# Mainsch.net
KiCad netlist of a schematic drawn in EAGLE
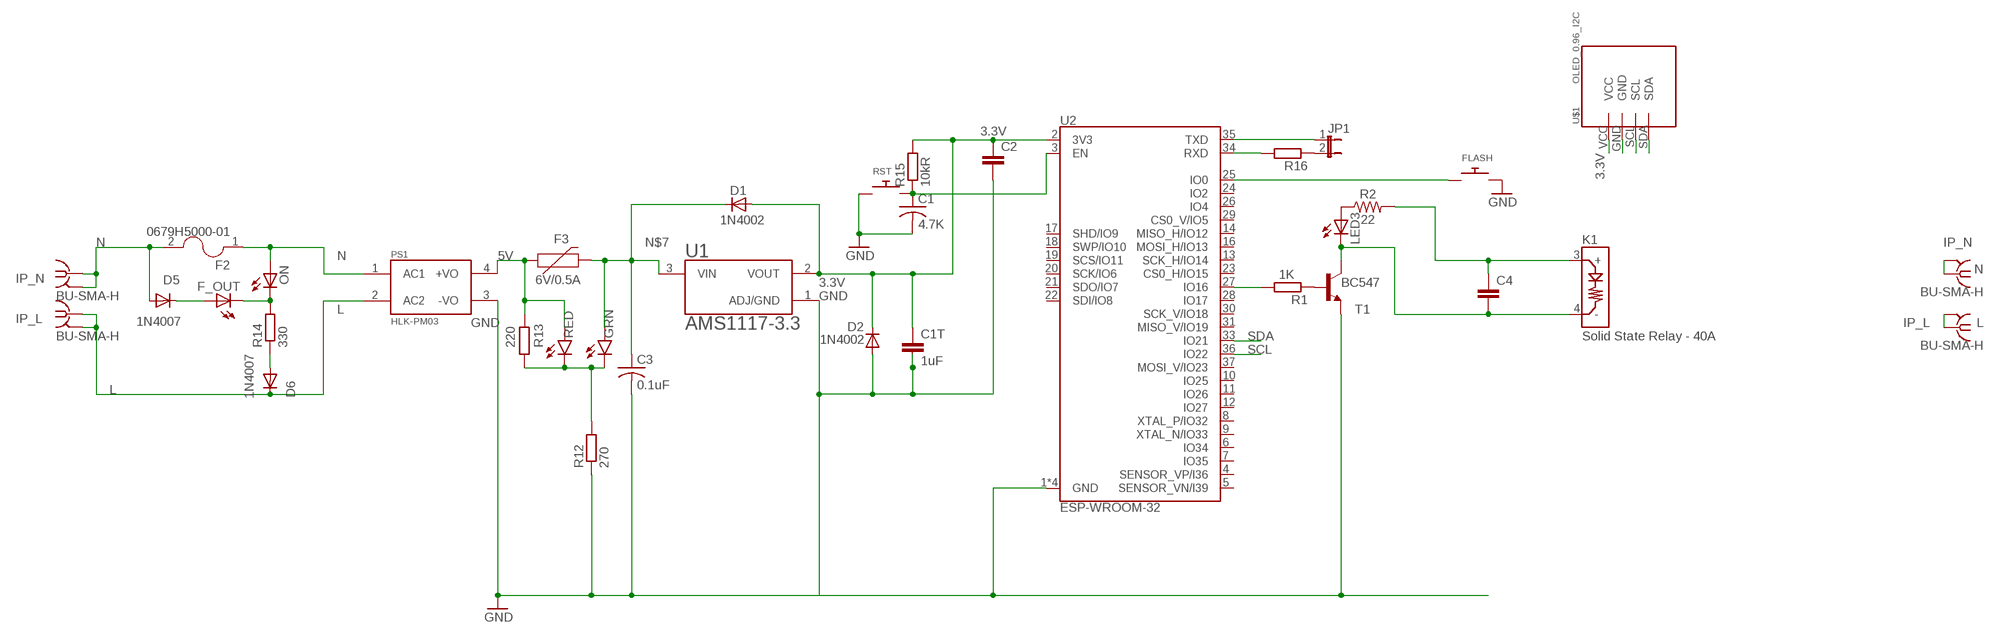
[diagram p0: schematic, sheet 1]

(export (version "E")
  (design (tool "Eeschema 10.0.6"))
  (components
    (comp (ref "C1")
      (value "4.7K")
      (footprint "eagle-import:C0805K")
      (libsource (lib "eagle-import") (part "C-USC0805K"))
    )
    (comp (ref "C1T")
      (value "1uF")
      (footprint "eagle-import:C0805")
      (libsource (lib "eagle-import") (part "C-EUC0805"))
    )
    (comp (ref "C2")
      (value "C-EUC0805")
      (footprint "eagle-import:C0805")
      (libsource (lib "eagle-import") (part "C-EUC0805"))
    )
    (comp (ref "C3")
      (value "0.1uF")
      (footprint "eagle-import:C0805K")
      (libsource (lib "eagle-import") (part "C-USC0805K"))
    )
    (comp (ref "C4")
      (value "C-EUC0805")
      (footprint "eagle-import:C0805")
      (libsource (lib "eagle-import") (part "C-EUC0805"))
    )
    (comp (ref "D1")
      (value "1N4002")
      (footprint "eagle-import:DO41-10")
      (libsource (lib "eagle-import") (part "diode_1N4004"))
    )
    (comp (ref "D2")
      (value "1N4002")
      (footprint "eagle-import:DO41-10")
      (libsource (lib "eagle-import") (part "diode_1N4004"))
    )
    (comp (ref "D5")
      (value "1N4007")
      (footprint "eagle-import:DO41-10")
      (libsource (lib "eagle-import") (part "1N4004"))
    )
    (comp (ref "D6")
      (value "1N4007")
      (footprint "eagle-import:DO41-10")
      (libsource (lib "eagle-import") (part "1N4004"))
    )
    (comp (ref "F2")
      (value "0679H5000-01")
      (footprint "eagle-import:FUSC6125X279N")
      (fields (field (name "MF") "Bel Fuse"))
      (libsource (lib "eagle-import") (part "0679H5000-01"))
    )
    (comp (ref "F3")
      (value "6V/0.5A")
      (footprint "eagle-import:1206")
      (libsource (lib "eagle-import") (part "PPTC_6V500MA-2"))
    )
    (comp (ref "FLASH")
      (value "SWITCH_PUSHBUTTONC&K_KSS")
      (footprint "eagle-import:BTN_CK_KSS")
      (libsource (lib "eagle-import") (part "SWITCH_PUSHBUTTONC&K_KSS"))
    )
    (comp (ref "F_OUT")
      (value "LEDCHIPLED_1206")
      (footprint "eagle-import:CHIPLED_1206")
      (libsource (lib "eagle-import") (part "LEDCHIPLED_1206"))
    )
    (comp (ref "GRN")
      (value "LED1206")
      (footprint "eagle-import:LED-1206")
      (libsource (lib "eagle-import") (part "LED1206"))
    )
    (comp (ref "IP_L")
      (value "BU-SMA-H")
      (footprint "eagle-import:BU-SMA-H")
      (libsource (lib "eagle-import") (part "BU-SMA-H"))
    )
    (comp (ref "IP_N")
      (value "BU-SMA-H")
      (footprint "eagle-import:BU-SMA-H")
      (libsource (lib "eagle-import") (part "BU-SMA-H"))
    )
    (comp (ref "JP1")
      (value "JP1E")
      (footprint "eagle-import:JP1")
      (libsource (lib "eagle-import") (part "JP1E"))
    )
    (comp (ref "K1")
      (value "Solid State Relay - 40A")
      (footprint "eagle-import:SSR-40DA-H")
      (libsource (lib "eagle-import") (part "SOLID_STATE_RELAY_SSR-40DA-H"))
    )
    (comp (ref "L")
      (value "BU-SMA-H")
      (footprint "eagle-import:BU-SMA-H")
      (libsource (lib "eagle-import") (part "BU-SMA-H"))
    )
    (comp (ref "LED3")
      (value "LEDCHIPLED_1206")
      (footprint "eagle-import:CHIPLED_1206")
      (libsource (lib "eagle-import") (part "LEDCHIPLED_1206"))
    )
    (comp (ref "N")
      (value "BU-SMA-H")
      (footprint "eagle-import:BU-SMA-H")
      (libsource (lib "eagle-import") (part "BU-SMA-H"))
    )
    (comp (ref "ON")
      (value "LEDCHIPLED_1206")
      (footprint "eagle-import:CHIPLED_1206")
      (libsource (lib "eagle-import") (part "LEDCHIPLED_1206"))
    )
    (comp (ref "PS1")
      (value "HLK-PM03")
      (footprint "eagle-import:CONV_HLK-PM03")
      (fields (field (name "MF") "Hi-link"))
      (libsource (lib "eagle-import") (part "HLK-PM03"))
    )
    (comp (ref "R1")
      (value "1K")
      (footprint "eagle-import:R1206")
      (libsource (lib "eagle-import") (part "resistor_348_R-EU_R1206"))
    )
    (comp (ref "R2")
      (value "22")
      (footprint "eagle-import:0603")
      (libsource (lib "eagle-import") (part "22OHM-0603-1/10W-1%"))
    )
    (comp (ref "R12")
      (value "270")
      (footprint "eagle-import:R0805")
      (libsource (lib "eagle-import") (part "R-EU_R0805"))
    )
    (comp (ref "R13")
      (value "220")
      (footprint "eagle-import:R0805")
      (libsource (lib "eagle-import") (part "R-EU_R0805"))
    )
    (comp (ref "R14")
      (value "330")
      (footprint "eagle-import:R0805")
      (libsource (lib "eagle-import") (part "R-EU_R0805"))
    )
    (comp (ref "R15")
      (value "10kR")
      (footprint "eagle-import:R0805")
      (libsource (lib "eagle-import") (part "R-EU_R0805"))
    )
    (comp (ref "R16")
      (value "R-EU_R0805")
      (footprint "eagle-import:R0805")
      (libsource (lib "eagle-import") (part "R-EU_R0805"))
    )
    (comp (ref "RED")
      (value "LED1206")
      (footprint "eagle-import:LED-1206")
      (libsource (lib "eagle-import") (part "LED1206"))
    )
    (comp (ref "RST")
      (value "SWITCH_PUSHBUTTONC&K_KSS")
      (footprint "eagle-import:BTN_CK_KSS")
      (libsource (lib "eagle-import") (part "SWITCH_PUSHBUTTONC&K_KSS"))
    )
    (comp (ref "T1")
      (value "BC547")
      (footprint "eagle-import:TO92")
      (libsource (lib "eagle-import") (part "BC547"))
    )
    (comp (ref "U$1")
      (value "OLED_0.96_I2C")
      (footprint "eagle-import:OLED_0.96_I2C")
      (libsource (lib "eagle-import") (part "OLED_0.96_I2C"))
    )
    (comp (ref "U1")
      (value "AMS1117-3.3")
      (footprint "eagle-import:SOT229P700X180-4N")
      (fields (field (name "MF") "AMD"))
      (libsource (lib "eagle-import") (part "AMS1117-3.3"))
    )
    (comp (ref "U2")
      (value "ESP-WROOM-32")
      (footprint "eagle-import:ESP-WROOM-32")
      (libsource (lib "eagle-import") (part "ESP-WROOM-32"))
    )
  )
  (nets
    (net (code "1") (name "/3.3V") (class "Default")
      (node (ref "C1T") (pin "1") (pinfunction "1_1") (pintype "passive"))
      (node (ref "C2") (pin "1") (pinfunction "1_1") (pintype "passive"))
      (node (ref "D1") (pin "A") (pinfunction "A_A") (pintype "passive"))
      (node (ref "D2") (pin "C") (pinfunction "C_C") (pintype "passive"))
      (node (ref "R15") (pin "2") (pinfunction "2_2") (pintype "passive"))
      (node (ref "U$1") (pin "VCC") (pinfunction "VCC_VCC") (pintype "bidirectional"))
      (node (ref "U1") (pin "2") (pinfunction "VOUT_2") (pintype "output"))
      (node (ref "U2") (pin "2") (pinfunction "3V3_2") (pintype "bidirectional"))
    )
    (net (code "2") (name "/5V") (class "Default")
      (node (ref "F3") (pin "1") (pinfunction "1_1") (pintype "bidirectional"))
      (node (ref "PS1") (pin "4") (pinfunction "+VO_4") (pintype "output"))
      (node (ref "R13") (pin "2") (pinfunction "2_2") (pintype "passive"))
      (node (ref "RED") (pin "A") (pinfunction "A_A") (pintype "passive"))
    )
    (net (code "3") (name "/IP_L") (class "Default")
      (node (ref "L") (pin "1") (pinfunction "1_1") (pintype "passive"))
      (node (ref "L") (pin "2") (pinfunction "2_2") (pintype "passive"))
      (node (ref "L") (pin "3") (pinfunction "2_3") (pintype "passive"))
      (node (ref "L") (pin "4") (pinfunction "2_4") (pintype "passive"))
      (node (ref "L") (pin "5") (pinfunction "2_5") (pintype "passive"))
    )
    (net (code "4") (name "/IP_N") (class "Default")
      (node (ref "N") (pin "1") (pinfunction "1_1") (pintype "passive"))
      (node (ref "N") (pin "2") (pinfunction "2_2") (pintype "passive"))
      (node (ref "N") (pin "3") (pinfunction "2_3") (pintype "passive"))
      (node (ref "N") (pin "4") (pinfunction "2_4") (pintype "passive"))
      (node (ref "N") (pin "5") (pinfunction "2_5") (pintype "passive"))
    )
    (net (code "5") (name "/L") (class "Default")
      (node (ref "D6") (pin "C") (pinfunction "C_C") (pintype "passive"))
      (node (ref "IP_L") (pin "1") (pinfunction "1_1") (pintype "passive"))
      (node (ref "IP_L") (pin "2") (pinfunction "2_2") (pintype "passive"))
      (node (ref "IP_L") (pin "3") (pinfunction "2_3") (pintype "passive"))
      (node (ref "IP_L") (pin "4") (pinfunction "2_4") (pintype "passive"))
      (node (ref "IP_L") (pin "5") (pinfunction "2_5") (pintype "passive"))
      (node (ref "PS1") (pin "2") (pinfunction "AC2_2") (pintype "input"))
    )
    (net (code "6") (name "/N") (class "Default")
      (node (ref "D5") (pin "A") (pinfunction "A_A") (pintype "passive"))
      (node (ref "F2") (pin "1") (pinfunction "1_1") (pintype "passive"))
      (node (ref "F2") (pin "2") (pinfunction "2_2") (pintype "passive"))
      (node (ref "IP_N") (pin "1") (pinfunction "1_1") (pintype "passive"))
      (node (ref "IP_N") (pin "2") (pinfunction "2_2") (pintype "passive"))
      (node (ref "IP_N") (pin "3") (pinfunction "2_3") (pintype "passive"))
      (node (ref "IP_N") (pin "4") (pinfunction "2_4") (pintype "passive"))
      (node (ref "IP_N") (pin "5") (pinfunction "2_5") (pintype "passive"))
      (node (ref "ON") (pin "A") (pinfunction "A_A") (pintype "passive"))
      (node (ref "PS1") (pin "1") (pinfunction "AC1_1") (pintype "input"))
    )
    (net (code "7") (name "/N$7") (class "Default")
      (node (ref "C3") (pin "1") (pinfunction "1_1") (pintype "passive"))
      (node (ref "D1") (pin "C") (pinfunction "C_C") (pintype "passive"))
      (node (ref "F3") (pin "2") (pinfunction "2_2") (pintype "bidirectional"))
      (node (ref "GRN") (pin "A") (pinfunction "A_A") (pintype "passive"))
      (node (ref "U1") (pin "3") (pinfunction "VIN_3") (pintype "input"))
    )
    (net (code "8") (name "/SCL") (class "Default")
      (node (ref "U$1") (pin "SCL") (pinfunction "SCL_SCL") (pintype "bidirectional"))
      (node (ref "U2") (pin "36") (pinfunction "IO22_36") (pintype "bidirectional"))
    )
    (net (code "9") (name "/SDA") (class "Default")
      (node (ref "U$1") (pin "SDA") (pinfunction "SDA_SDA") (pintype "bidirectional"))
      (node (ref "U2") (pin "33") (pinfunction "IO21_33") (pintype "bidirectional"))
    )
    (net (code "10") (name "GND") (class "Default")
      (node (ref "C1") (pin "2") (pinfunction "2_2") (pintype "passive"))
      (node (ref "C1T") (pin "2") (pinfunction "2_2") (pintype "passive"))
      (node (ref "C2") (pin "2") (pinfunction "2_2") (pintype "passive"))
      (node (ref "C3") (pin "2") (pinfunction "2_2") (pintype "passive"))
      (node (ref "D2") (pin "A") (pinfunction "A_A") (pintype "passive"))
      (node (ref "FLASH") (pin "P$2") (pinfunction "P$2_P$2") (pintype "passive"))
      (node (ref "PS1") (pin "3") (pinfunction "-VO_3") (pintype "output"))
      (node (ref "R12") (pin "1") (pinfunction "1_1") (pintype "passive"))
      (node (ref "RST") (pin "P$1") (pinfunction "P$1_P$1") (pintype "passive"))
      (node (ref "T1") (pin "1") (pinfunction "E_1") (pintype "passive"))
      (node (ref "U$1") (pin "GND") (pinfunction "GND_GND") (pintype "bidirectional"))
      (node (ref "U1") (pin "1") (pinfunction "ADJ/GND_1") (pintype "power_in"))
      (node (ref "U2") (pin "1") (pinfunction "GND_1") (pintype "bidirectional"))
      (node (ref "U2") (pin "15") (pinfunction "GND_15") (pintype "bidirectional"))
      (node (ref "U2") (pin "38") (pinfunction "GND_38") (pintype "bidirectional"))
      (node (ref "U2") (pin "GND") (pinfunction "GND_GND") (pintype "bidirectional"))
    )
    (net (code "11") (name "Net-(D5-PadC)") (class "Default")
      (node (ref "D5") (pin "C") (pinfunction "C_C") (pintype "passive"))
      (node (ref "F_OUT") (pin "A") (pinfunction "A_A") (pintype "passive"))
    )
    (net (code "12") (name "Net-(D6-PadA)") (class "Default")
      (node (ref "D6") (pin "A") (pinfunction "A_A") (pintype "passive"))
      (node (ref "R14") (pin "1") (pinfunction "1_1") (pintype "passive"))
    )
    (net (code "13") (name "Net-(F_OUT-PadC)") (class "Default")
      (node (ref "F_OUT") (pin "C") (pinfunction "C_C") (pintype "passive"))
      (node (ref "ON") (pin "C") (pinfunction "C_C") (pintype "passive"))
      (node (ref "R14") (pin "2") (pinfunction "2_2") (pintype "passive"))
    )
    (net (code "14") (name "Net-(GRN-PadC)") (class "Default")
      (node (ref "GRN") (pin "C") (pinfunction "C_C") (pintype "passive"))
      (node (ref "R12") (pin "2") (pinfunction "2_2") (pintype "passive"))
      (node (ref "R13") (pin "1") (pinfunction "1_1") (pintype "passive"))
      (node (ref "RED") (pin "C") (pinfunction "C_C") (pintype "passive"))
    )
    (net (code "15") (name "Net-(JP1-Pad2)") (class "Default")
      (node (ref "JP1") (pin "2") (pinfunction "2_2") (pintype "passive"))
      (node (ref "R16") (pin "1") (pinfunction "1_1") (pintype "passive"))
    )
    (net (code "16") (name "Net-(K1-+)") (class "Default")
      (node (ref "C4") (pin "1") (pinfunction "1_1") (pintype "passive"))
      (node (ref "K1") (pin "3") (pinfunction "+_3") (pintype "bidirectional"))
      (node (ref "R2") (pin "2") (pinfunction "2_2") (pintype "passive"))
    )
    (net (code "17") (name "Net-(K1--)") (class "Default")
      (node (ref "C4") (pin "2") (pinfunction "2_2") (pintype "passive"))
      (node (ref "K1") (pin "4") (pinfunction "-_4") (pintype "bidirectional"))
      (node (ref "LED3") (pin "C") (pinfunction "C_C") (pintype "passive"))
      (node (ref "T1") (pin "3") (pinfunction "C_3") (pintype "passive"))
    )
    (net (code "18") (name "Net-(LED3-PadA)") (class "Default")
      (node (ref "LED3") (pin "A") (pinfunction "A_A") (pintype "passive"))
      (node (ref "R2") (pin "1") (pinfunction "1_1") (pintype "passive"))
    )
    (net (code "19") (name "Net-(T1-B)") (class "Default")
      (node (ref "R1") (pin "1") (pinfunction "1_1") (pintype "passive"))
      (node (ref "T1") (pin "2") (pinfunction "B_2") (pintype "passive"))
    )
    (net (code "20") (name "Net-(U2-EN)") (class "Default")
      (node (ref "C1") (pin "1") (pinfunction "1_1") (pintype "passive"))
      (node (ref "R15") (pin "1") (pinfunction "1_1") (pintype "passive"))
      (node (ref "RST") (pin "P$2") (pinfunction "P$2_P$2") (pintype "passive"))
      (node (ref "U2") (pin "3") (pinfunction "EN_3") (pintype "bidirectional"))
    )
    (net (code "21") (name "Net-(U2-IO0)") (class "Default")
      (node (ref "FLASH") (pin "P$1") (pinfunction "P$1_P$1") (pintype "passive"))
      (node (ref "U2") (pin "25") (pinfunction "IO0_25") (pintype "bidirectional"))
    )
    (net (code "22") (name "Net-(U2-IO16)") (class "Default")
      (node (ref "R1") (pin "2") (pinfunction "2_2") (pintype "passive"))
      (node (ref "U2") (pin "27") (pinfunction "IO16_27") (pintype "bidirectional"))
    )
    (net (code "23") (name "Net-(U2-RXD)") (class "Default")
      (node (ref "R16") (pin "2") (pinfunction "2_2") (pintype "passive"))
      (node (ref "U2") (pin "34") (pinfunction "RXD_34") (pintype "bidirectional"))
    )
    (net (code "24") (name "Net-(U2-TXD)") (class "Default")
      (node (ref "JP1") (pin "1") (pinfunction "1_1") (pintype "passive"))
      (node (ref "U2") (pin "35") (pinfunction "TXD_35") (pintype "bidirectional"))
    )
    (net (code "25") (name "unconnected-(U2-CS0_H{slash}IO15-Pad23)") (class "Default")
      (node (ref "U2") (pin "23") (pinfunction "CS0_H/IO15_23") (pintype "bidirectional"))
    )
    (net (code "26") (name "unconnected-(U2-CS0_V{slash}IO5-Pad29)") (class "Default")
      (node (ref "U2") (pin "29") (pinfunction "CS0_V/IO5_29") (pintype "bidirectional"))
    )
    (net (code "27") (name "unconnected-(U2-IO2-Pad24)") (class "Default")
      (node (ref "U2") (pin "24") (pinfunction "IO2_24") (pintype "bidirectional"))
    )
    (net (code "28") (name "unconnected-(U2-IO4-Pad26)") (class "Default")
      (node (ref "U2") (pin "26") (pinfunction "IO4_26") (pintype "bidirectional"))
    )
    (net (code "29") (name "unconnected-(U2-IO17-Pad28)") (class "Default")
      (node (ref "U2") (pin "28") (pinfunction "IO17_28") (pintype "bidirectional"))
    )
    (net (code "30") (name "unconnected-(U2-IO25-Pad10)") (class "Default")
      (node (ref "U2") (pin "10") (pinfunction "IO25_10") (pintype "bidirectional"))
    )
    (net (code "31") (name "unconnected-(U2-IO26-Pad11)") (class "Default")
      (node (ref "U2") (pin "11") (pinfunction "IO26_11") (pintype "bidirectional"))
    )
    (net (code "32") (name "unconnected-(U2-IO27-Pad12)") (class "Default")
      (node (ref "U2") (pin "12") (pinfunction "IO27_12") (pintype "bidirectional"))
    )
    (net (code "33") (name "unconnected-(U2-IO34-Pad6)") (class "Default")
      (node (ref "U2") (pin "6") (pinfunction "IO34_6") (pintype "bidirectional"))
    )
    (net (code "34") (name "unconnected-(U2-IO35-Pad7)") (class "Default")
      (node (ref "U2") (pin "7") (pinfunction "IO35_7") (pintype "bidirectional"))
    )
    (net (code "35") (name "unconnected-(U2-MISO_H{slash}IO12-Pad14)") (class "Default")
      (node (ref "U2") (pin "14") (pinfunction "MISO_H/IO12_14") (pintype "bidirectional"))
    )
    (net (code "36") (name "unconnected-(U2-MISO_V{slash}IO19-Pad31)") (class "Default")
      (node (ref "U2") (pin "31") (pinfunction "MISO_V/IO19_31") (pintype "bidirectional"))
    )
    (net (code "37") (name "unconnected-(U2-MOSI_H{slash}IO13-Pad16)") (class "Default")
      (node (ref "U2") (pin "16") (pinfunction "MOSI_H/IO13_16") (pintype "bidirectional"))
    )
    (net (code "38") (name "unconnected-(U2-MOSI_V{slash}IO23-Pad37)") (class "Default")
      (node (ref "U2") (pin "37") (pinfunction "MOSI_V/IO23_37") (pintype "bidirectional"))
    )
    (net (code "39") (name "unconnected-(U2-SCK_H{slash}IO14-Pad13)") (class "Default")
      (node (ref "U2") (pin "13") (pinfunction "SCK_H/IO14_13") (pintype "bidirectional"))
    )
    (net (code "40") (name "unconnected-(U2-SCK_V{slash}IO18-Pad30)") (class "Default")
      (node (ref "U2") (pin "30") (pinfunction "SCK_V/IO18_30") (pintype "bidirectional"))
    )
    (net (code "41") (name "unconnected-(U2-SCK{slash}IO6-Pad20)") (class "Default")
      (node (ref "U2") (pin "20") (pinfunction "SCK/IO6_20") (pintype "bidirectional"))
    )
    (net (code "42") (name "unconnected-(U2-SCS{slash}IO11-Pad19)") (class "Default")
      (node (ref "U2") (pin "19") (pinfunction "SCS/IO11_19") (pintype "bidirectional"))
    )
    (net (code "43") (name "unconnected-(U2-SDI{slash}IO8-Pad22)") (class "Default")
      (node (ref "U2") (pin "22") (pinfunction "SDI/IO8_22") (pintype "bidirectional"))
    )
    (net (code "44") (name "unconnected-(U2-SDO{slash}IO7-Pad21)") (class "Default")
      (node (ref "U2") (pin "21") (pinfunction "SDO/IO7_21") (pintype "bidirectional"))
    )
    (net (code "45") (name "unconnected-(U2-SENSOR_VN{slash}I39-Pad5)") (class "Default")
      (node (ref "U2") (pin "5") (pinfunction "SENSOR_VN/I39_5") (pintype "bidirectional"))
    )
    (net (code "46") (name "unconnected-(U2-SENSOR_VP{slash}I36-Pad4)") (class "Default")
      (node (ref "U2") (pin "4") (pinfunction "SENSOR_VP/I36_4") (pintype "bidirectional"))
    )
    (net (code "47") (name "unconnected-(U2-SHD{slash}IO9-Pad17)") (class "Default")
      (node (ref "U2") (pin "17") (pinfunction "SHD/IO9_17") (pintype "bidirectional"))
    )
    (net (code "48") (name "unconnected-(U2-SWP{slash}IO10-Pad18)") (class "Default")
      (node (ref "U2") (pin "18") (pinfunction "SWP/IO10_18") (pintype "bidirectional"))
    )
    (net (code "49") (name "unconnected-(U2-XTAL_N{slash}IO33-Pad9)") (class "Default")
      (node (ref "U2") (pin "9") (pinfunction "XTAL_N/IO33_9") (pintype "bidirectional"))
    )
    (net (code "50") (name "unconnected-(U2-XTAL_P{slash}IO32-Pad8)") (class "Default")
      (node (ref "U2") (pin "8") (pinfunction "XTAL_P/IO32_8") (pintype "bidirectional"))
    )
  )
)
